# SCH_NFC-Business-card_2024-03-30.net
KiCad netlist of a schematic drawn in EasyEDA
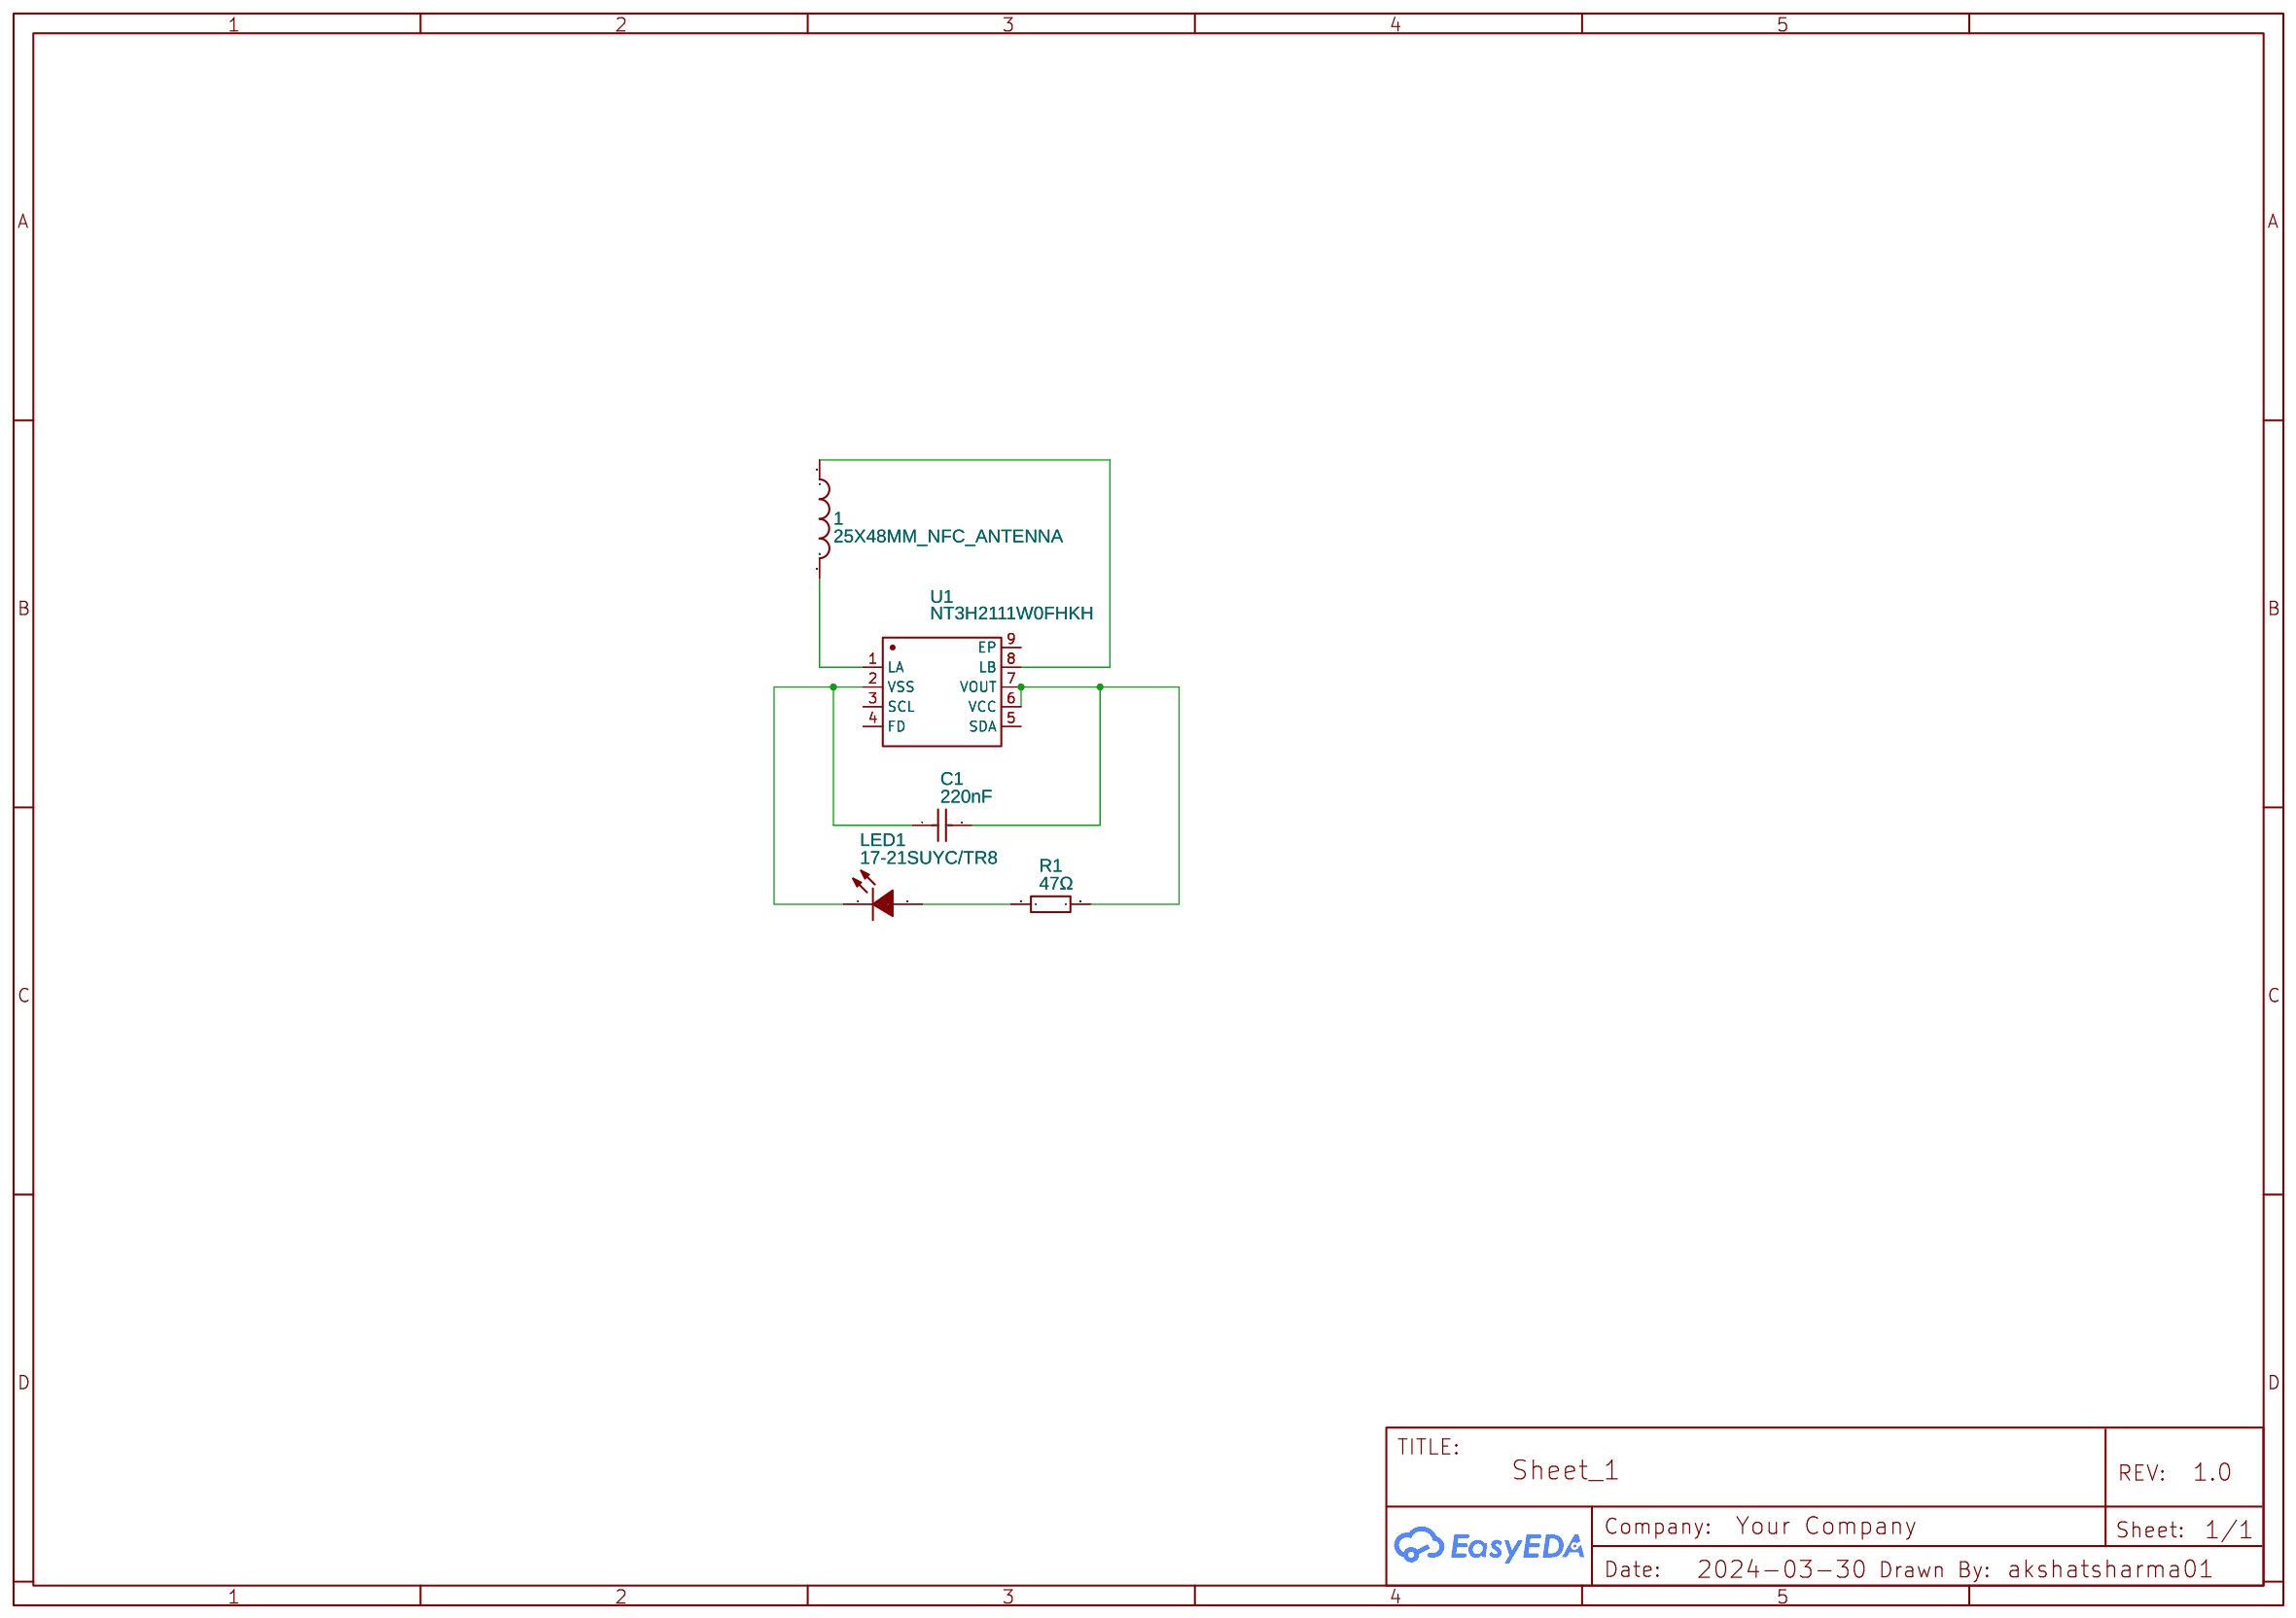
[diagram p0: schematic sheet]

(export (version "E")
  (design (tool "Eeschema 10.0.6"))
  (components
    (comp (ref "1") (value "25X48MM_NFC_ANTENNA") (libsource (lib "") (part "25X48MM_NFC_ANTENNA")))
    (comp (ref "C1")
      (value "220nF")
      (fields
        (field (name "Manufacturer Part") "CL10B224KA8NNNC")
        (field (name "Manufacturer") "SAMSUNG(三星)")
      )
      (libsource (lib "") (part "CL10B224KA8NNNC"))
    )
    (comp (ref "LED1")
      (value "17-21SUYC/TR8")
      (fields (field (name "Manufacturer Part") "KT-0805黄灯") (field (name "Manufacturer") "KENTO"))
      (libsource (lib "") (part "17-21SUYC/TR8"))
    )
    (comp (ref "R1")
      (value "47Ω")
      (fields
        (field (name "Manufacturer Part") "0603WAF470JT5E")
        (field (name "Manufacturer") "UNI-ROYAL(厚声)")
      )
      (libsource (lib "") (part "0603WAF470JT5E"))
    )
    (comp (ref "U1")
      (value "NT3H2111W0FHKH")
      (fields (field (name "Manufacturer") "NXP(恩智浦)"))
      (libsource (lib "") (part "NT3H2111W0FHKH"))
    )
  )
  (nets
    (net (code "1") (name "Net-(LED1-+)") (class "Default")
      (node (ref "LED1") (pin "1") (pinfunction "+_1") (pintype "unspecified"))
      (node (ref "R1") (pin "1") (pinfunction "1_1") (pintype "input"))
    )
    (net (code "2") (name "Net-(LED1--)") (class "Default")
      (node (ref "C1") (pin "1") (pinfunction "1_1") (pintype "input"))
      (node (ref "LED1") (pin "2") (pinfunction "-_2") (pintype "unspecified"))
      (node (ref "U1") (pin "2") (pinfunction "VSS_2") (pintype "unspecified"))
    )
    (net (code "3") (name "Net-(U1-LA)") (class "Default")
      (node (ref "1") (pin "P$2") (pinfunction "P$2_P$2") (pintype "bidirectional"))
      (node (ref "U1") (pin "1") (pinfunction "LA_1") (pintype "unspecified"))
    )
    (net (code "4") (name "Net-(U1-LB)") (class "Default")
      (node (ref "1") (pin "P$1") (pinfunction "P$1_P$1") (pintype "bidirectional"))
      (node (ref "U1") (pin "8") (pinfunction "LB_8") (pintype "unspecified"))
    )
    (net (code "5") (name "Net-(U1-VCC)") (class "Default")
      (node (ref "C1") (pin "2") (pinfunction "2_2") (pintype "input"))
      (node (ref "R1") (pin "2") (pinfunction "2_2") (pintype "input"))
      (node (ref "U1") (pin "6") (pinfunction "VCC_6") (pintype "unspecified"))
      (node (ref "U1") (pin "7") (pinfunction "VOUT_7") (pintype "unspecified"))
    )
    (net (code "6") (name "unconnected-(U1-EP-Pad9)") (class "Default")
      (node (ref "U1") (pin "9") (pinfunction "EP_9") (pintype "unspecified"))
    )
    (net (code "7") (name "unconnected-(U1-FD-Pad4)") (class "Default")
      (node (ref "U1") (pin "4") (pinfunction "FD_4") (pintype "unspecified"))
    )
    (net (code "8") (name "unconnected-(U1-SCL-Pad3)") (class "Default")
      (node (ref "U1") (pin "3") (pinfunction "SCL_3") (pintype "unspecified"))
    )
    (net (code "9") (name "unconnected-(U1-SDA-Pad5)") (class "Default")
      (node (ref "U1") (pin "5") (pinfunction "SDA_5") (pintype "unspecified"))
    )
  )
)
